# Simon_game.net
KiCad netlist of a schematic drawn in Altium Designer
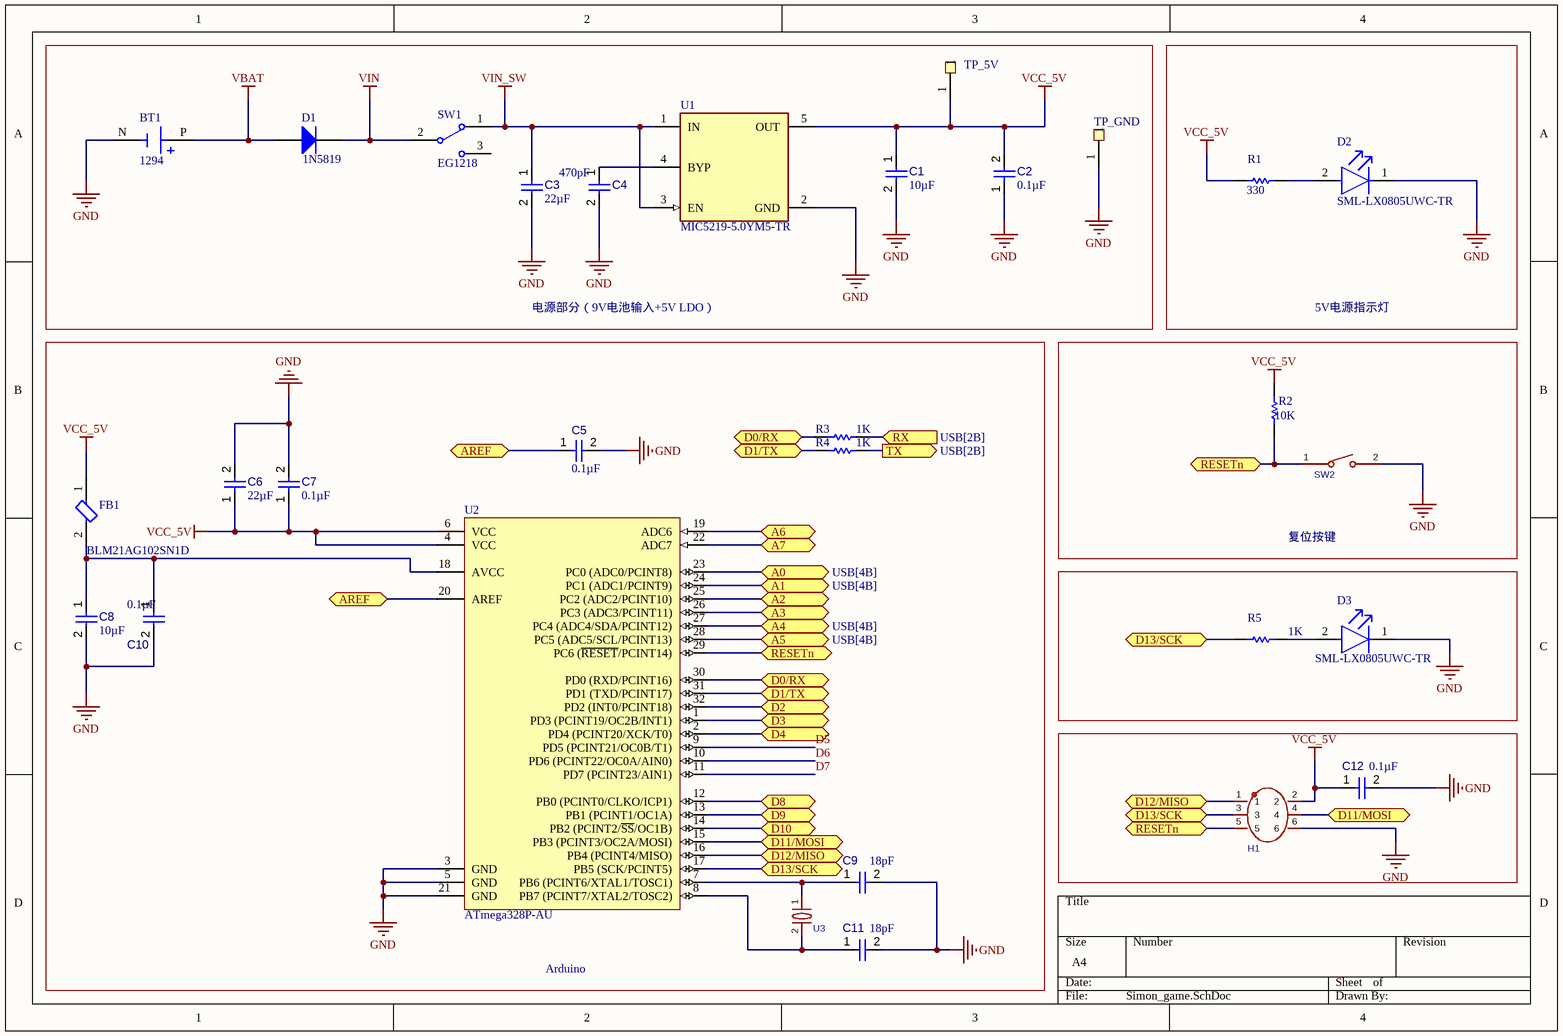
[diagram p0: Simon_game.SchDoc]

(export (version "E")
  (design (tool "Eeschema 10.0.6"))
  (components
    (comp (ref "BT1")
      (value "1294")
      (footprint "BAT_1294")
      (description "9 Volt Battery Holder- PC Terminals")
      (fields (field (name "MF") "Keystone Electronics"))
      (libsource (lib "keystone1294电池底座") (part "1294"))
    )
    (comp (ref "C1")
      (value "10µF")
      (footprint "CAPC2013X135X45NL10T25")
      (description "Chip Capacitor, 10 uF, +/- 10%, 16 V, 0805 (2012 Metric)")
      (fields (field (name "TOLERANCE") "10%") (field (name "Comment") "Capacitor 10 uF +/- 10% 16 V 0805"))
      (libsource (lib "新宇 付") (part "CAP-NP-2"))
    )
    (comp (ref "C2")
      (value "0.1µF")
      (footprint "CAPC2013X135X45NL10T25")
      (description "Chip Capacitor, 10 uF, +/- 10%, 16 V, 0805 (2012 Metric)")
      (fields (field (name "TOLERANCE") "10%") (field (name "Comment") "Capacitor 10 uF +/- 10% 16 V 0805"))
      (libsource (lib "新宇 付") (part "CAP-NP-2"))
    )
    (comp (ref "C3")
      (value "22µF")
      (footprint "CAPC2013X135X45NL10T25")
      (description "Chip Capacitor, 10 uF, +/- 10%, 16 V, 0805 (2012 Metric)")
      (fields (field (name "TOLERANCE") "10%") (field (name "Comment") "Capacitor 10 uF +/- 10% 16 V 0805"))
      (libsource (lib "新宇 付") (part "CAP-NP-2"))
    )
    (comp (ref "C4")
      (value "470pF")
      (footprint "CAPC2013X135X45NL10T25")
      (description "Chip Capacitor, 10 uF, +/- 10%, 16 V, 0805 (2012 Metric)")
      (fields (field (name "TOLERANCE") "10%") (field (name "Comment") "Capacitor 10 uF +/- 10% 16 V 0805"))
      (libsource (lib "新宇 付") (part "CAP-NP-2"))
    )
    (comp (ref "C5")
      (value "0.1µF")
      (footprint "CAPC2013X135X45NL10T25")
      (description "Chip Capacitor, 10 uF, +/- 10%, 16 V, 0805 (2012 Metric)")
      (fields (field (name "TOLERANCE") "10%") (field (name "Comment") "Capacitor 10 uF +/- 10% 16 V 0805"))
      (libsource (lib "新宇 付") (part "CAP-NP-2"))
    )
    (comp (ref "C6")
      (value "22µF")
      (footprint "CAPC2013X135X45NL10T25")
      (description "Chip Capacitor, 10 uF, +/- 10%, 16 V, 0805 (2012 Metric)")
      (fields (field (name "TOLERANCE") "10%") (field (name "Comment") "Capacitor 10 uF +/- 10% 16 V 0805"))
      (libsource (lib "新宇 付") (part "CAP-NP-2"))
    )
    (comp (ref "C7")
      (value "0.1µF")
      (footprint "CAPC2013X135X45NL10T25")
      (description "Chip Capacitor, 10 uF, +/- 10%, 16 V, 0805 (2012 Metric)")
      (fields (field (name "TOLERANCE") "10%") (field (name "Comment") "Capacitor 10 uF +/- 10% 16 V 0805"))
      (libsource (lib "新宇 付") (part "CAP-NP-2"))
    )
    (comp (ref "C8")
      (value "10µF")
      (footprint "CAPC2013X135X45NL10T25")
      (description "Chip Capacitor, 10 uF, +/- 10%, 16 V, 0805 (2012 Metric)")
      (fields (field (name "TOLERANCE") "10%") (field (name "Comment") "Capacitor 10 uF +/- 10% 16 V 0805"))
      (libsource (lib "新宇 付") (part "CAP-NP-2"))
    )
    (comp (ref "C9")
      (value "18pF")
      (footprint "CAPC2013X135X45NL10T25")
      (description "Chip Capacitor, 10 uF, +/- 10%, 16 V, 0805 (2012 Metric)")
      (fields (field (name "TOLERANCE") "10%") (field (name "Comment") "Capacitor 10 uF +/- 10% 16 V 0805"))
      (libsource (lib "新宇 付") (part "CAP-NP-2"))
    )
    (comp (ref "C10")
      (value "0.1µF")
      (footprint "CAPC2013X135X45NL10T25")
      (description "Chip Capacitor, 10 uF, +/- 10%, 16 V, 0805 (2012 Metric)")
      (fields (field (name "TOLERANCE") "10%") (field (name "Comment") "Capacitor 10 uF +/- 10% 16 V 0805"))
      (libsource (lib "新宇 付") (part "CAP-NP-2"))
    )
    (comp (ref "C11")
      (value "18pF")
      (footprint "CAPC2013X135X45NL10T25")
      (description "Chip Capacitor, 10 uF, +/- 10%, 16 V, 0805 (2012 Metric)")
      (fields (field (name "TOLERANCE") "10%") (field (name "Comment") "Capacitor 10 uF +/- 10% 16 V 0805"))
      (libsource (lib "新宇 付") (part "CAP-NP-2"))
    )
    (comp (ref "C12")
      (value "0.1µF")
      (footprint "CAPC2013X135X45NL10T25")
      (description "Chip Capacitor, 10 uF, +/- 10%, 16 V, 0805 (2012 Metric)")
      (fields (field (name "TOLERANCE") "10%") (field (name "Comment") "Capacitor 10 uF +/- 10% 16 V 0805"))
      (libsource (lib "新宇 付") (part "CAP-NP-2"))
    )
    (comp (ref "D1")
      (value "1N5819")
      (footprint "ONSC-AXIAL_LEAD-2-59-10_P")
      (description "Low Drop Power Schottky Rectifier, 40 V, 1 A, 2-Pin DO-41, RoHS")
      (fields (field (name "MANUFACTURER") "ON Semiconductor"))
      (libsource (lib "新宇 付") (part "D-AK-2"))
    )
    (comp (ref "D2")
      (value "SML-LX0805UWC-TR")
      (footprint "FP-SML-LX0805UWC-TR-MFG")
      (description "SML-LX0805UWC-TR White LED, 0805 Diffused, Rectangle Lens SMD package")
      (libsource (lib "Altium Content Vault") (part "8706943c75ba83719d021d2fdc84c58"))
    )
    (comp (ref "D3")
      (value "SML-LX0805UWC-TR")
      (footprint "FP-SML-LX0805UWC-TR-MFG")
      (description "SML-LX0805UWC-TR White LED, 0805 Diffused, Rectangle Lens SMD package")
      (libsource (lib "Altium Content Vault") (part "8706943c75ba83719d021d2fdc84c58"))
    )
    (comp (ref "FB1")
      (value "BLM21AG102SN1D")
      (footprint "FP-BLM21-0_2-t0_85-e0_5-MFG")
      (description "Chip Ferrite Bead, 0805, 1000Ω @ 100MHz, 0.27Ω, 25%, 600mA")
      (fields (field (name "TOLERANCE") "25%"))
      (libsource (lib "Altium Content Vault") (part "5f30dd21d616792df468990f7003faa"))
    )
    (comp (ref "H1")
      (value "PM2.54-2*3")
      (footprint "HDR-TH_6P-P2.54-V-F-R2-C3-S2.54")
      (libsource (lib "排母 2x3 2.54mm") (part "PM2.54-2*3"))
    )
    (comp (ref "R1")
      (value "330")
      (footprint "RESC2013X50X35ML15T15")
      (description "Chip Resistor, 0 Ohm, +/- 1%, 125 mW, -55 to 155 degC, 0805 (2012 Metric)")
      (fields (field (name "TOLERANCE") "1%") (field (name "POWER") "125mW"))
      (libsource (lib "新宇 付") (part "RES-2"))
    )
    (comp (ref "R2")
      (value "10K")
      (footprint "RESC2013X50X35ML15T15")
      (description "Chip Resistor, 0 Ohm, +/- 1%, 125 mW, -55 to 155 degC, 0805 (2012 Metric)")
      (fields (field (name "TOLERANCE") "1%") (field (name "POWER") "125mW"))
      (libsource (lib "新宇 付") (part "RES-2"))
    )
    (comp (ref "R3")
      (value "1K")
      (footprint "RESC2013X50X35ML15T15")
      (description "Chip Resistor, 0 Ohm, +/- 1%, 125 mW, -55 to 155 degC, 0805 (2012 Metric)")
      (fields (field (name "TOLERANCE") "1%") (field (name "POWER") "125mW"))
      (libsource (lib "新宇 付") (part "RES-2"))
    )
    (comp (ref "R4")
      (value "1K")
      (footprint "RESC2013X50X35ML15T15")
      (description "Chip Resistor, 0 Ohm, +/- 1%, 125 mW, -55 to 155 degC, 0805 (2012 Metric)")
      (fields (field (name "TOLERANCE") "1%") (field (name "POWER") "125mW"))
      (libsource (lib "新宇 付") (part "RES-2"))
    )
    (comp (ref "R5")
      (value "1K")
      (footprint "RESC2013X50X35ML15T15")
      (description "Chip Resistor, 0 Ohm, +/- 1%, 125 mW, -55 to 155 degC, 0805 (2012 Metric)")
      (fields (field (name "TOLERANCE") "1%") (field (name "POWER") "125mW"))
      (libsource (lib "新宇 付") (part "RES-2"))
    )
    (comp (ref "SW1")
      (value "EG1218")
      (footprint "ESWI-EG1218_V")
      (description "Slide Switch, 500 V, -20 to 70 degC, 3-Pin THD, RoHS")
      (libsource (lib "EG1218单刀双掷滑动开关") (part "CMP-1696-00002-1"))
    )
    (comp (ref "SW2")
      (value "TS-1088-AR02016")
      (footprint "SW-SMD_L3.9-W3.0-P4.45")
      (libsource (lib "Click_switch") (part "TS-1088-AR02016"))
    )
    (comp (ref "TP_5V")
      (value "TP_5V")
      (footprint "PCBComponent_1")
      (libsource (lib "testpoint") (part "Component_1"))
    )
    (comp (ref "TP_GND")
      (value "Component_1")
      (footprint "PCBComponent_1")
      (libsource (lib "testpoint") (part "Component_1"))
    )
    (comp (ref "U1")
      (value "MIC5219-5.0YM5-TR")
      (footprint "FP-SOT23-5LD-PL-1-MFG")
      (description "IC REG LINEAR 5V 500MA SOT23-5")
      (fields
        (field (name "OCTOPART") "https://octopart.com/mic5219-5.0ym5-tr-microchip-66802269")
        (field (name "MANUFACTURER") "Microchip Technology")
      )
      (libsource (lib "Altium Content Vault") (part "ef5decc81e5e4ee52dbbc9c70b739cf"))
    )
    (comp (ref "U2")
      (value "ATmega328P-AU")
      (footprint "32A_M")
      (libsource (lib "Altium Content Vault") (part "MC-8B-ATM48-SQ32"))
    )
    (comp (ref "U3")
      (value "ABLS-12.000MHZ-B4H-T")
      (footprint "CRYSTAL-SMD_L11.4-W4.7-LS12.7")
      (libsource (lib "12MHz_crystal_oscillator") (part "ABLS-12.000MHZ-B4H-T"))
    )
  )
  (nets
    (net (code "1") (name "/A0") (class "Default")
      (node (ref "U2") (pin "23") (pinfunction "PC0_(ADC0/PCINT8)_23") (pintype "bidirectional"))
    )
    (net (code "2") (name "/A1") (class "Default")
      (node (ref "U2") (pin "24") (pinfunction "PC1_(ADC1/PCINT9)_24") (pintype "bidirectional"))
    )
    (net (code "3") (name "/A2") (class "Default")
      (node (ref "U2") (pin "25") (pinfunction "PC2_(ADC2/PCINT10)_25") (pintype "bidirectional"))
    )
    (net (code "4") (name "/A3") (class "Default")
      (node (ref "U2") (pin "26") (pinfunction "PC3_(ADC3/PCINT11)_26") (pintype "bidirectional"))
    )
    (net (code "5") (name "/A4") (class "Default")
      (node (ref "U2") (pin "27") (pinfunction "PC4_(ADC4/SDA/PCINT12)_27") (pintype "bidirectional"))
    )
    (net (code "6") (name "/A5") (class "Default")
      (node (ref "U2") (pin "28") (pinfunction "PC5_(ADC5/SCL/PCINT13)_28") (pintype "bidirectional"))
    )
    (net (code "7") (name "/A6") (class "Default")
      (node (ref "U2") (pin "19") (pinfunction "ADC6_19") (pintype "input"))
    )
    (net (code "8") (name "/A7") (class "Default")
      (node (ref "U2") (pin "22") (pinfunction "ADC7_22") (pintype "input"))
    )
    (net (code "9") (name "/AREF") (class "Default")
      (node (ref "C5") (pin "1") (pinfunction "1_1") (pintype "passive"))
      (node (ref "U2") (pin "20") (pinfunction "AREF_20") (pintype "passive"))
    )
    (net (code "10") (name "/D0{slash}RX") (class "Default")
      (node (ref "R3") (pin "1") (pinfunction "1_1") (pintype "passive"))
      (node (ref "U2") (pin "30") (pinfunction "PD0_(RXD/PCINT16)_30") (pintype "bidirectional"))
    )
    (net (code "11") (name "/D1{slash}TX") (class "Default")
      (node (ref "R4") (pin "1") (pinfunction "1_1") (pintype "passive"))
      (node (ref "U2") (pin "31") (pinfunction "PD1_(TXD/PCINT17)_31") (pintype "bidirectional"))
    )
    (net (code "12") (name "/D2") (class "Default")
      (node (ref "U2") (pin "32") (pinfunction "PD2_(INT0/PCINT18)_32") (pintype "bidirectional"))
    )
    (net (code "13") (name "/D3") (class "Default")
      (node (ref "U2") (pin "1") (pinfunction "PD3_(PCINT19/OC2B/INT1)_1") (pintype "bidirectional"))
    )
    (net (code "14") (name "/D4") (class "Default")
      (node (ref "U2") (pin "2") (pinfunction "PD4_(PCINT20/XCK/T0)_2") (pintype "bidirectional"))
    )
    (net (code "15") (name "/D5") (class "Default")
      (node (ref "U2") (pin "9") (pinfunction "PD5_(PCINT21/OC0B/T1)_9") (pintype "bidirectional"))
    )
    (net (code "16") (name "/D6") (class "Default")
      (node (ref "U2") (pin "10") (pinfunction "PD6_(PCINT22/OC0A/AIN0)_10") (pintype "bidirectional"))
    )
    (net (code "17") (name "/D7") (class "Default")
      (node (ref "U2") (pin "11") (pinfunction "PD7_(PCINT23/AIN1)_11") (pintype "bidirectional"))
    )
    (net (code "18") (name "/D8") (class "Default")
      (node (ref "U2") (pin "12") (pinfunction "PB0_(PCINT0/CLKO/ICP1)_12") (pintype "bidirectional"))
    )
    (net (code "19") (name "/D9") (class "Default")
      (node (ref "U2") (pin "13") (pinfunction "PB1_(PCINT1/OC1A)_13") (pintype "bidirectional"))
    )
    (net (code "20") (name "/D10") (class "Default")
      (node (ref "U2") (pin "14") (pinfunction "PB2_(PCINT2/~{SS}/OC1B)_14") (pintype "bidirectional"))
    )
    (net (code "21") (name "/D11{slash}MOSI") (class "Default")
      (node (ref "H1") (pin "4") (pinfunction "4_4") (pintype "passive"))
      (node (ref "U2") (pin "15") (pinfunction "PB3_(PCINT3/OC2A/MOSI)_15") (pintype "bidirectional"))
    )
    (net (code "22") (name "/D12{slash}MISO") (class "Default")
      (node (ref "H1") (pin "1") (pinfunction "1_1") (pintype "passive"))
      (node (ref "U2") (pin "16") (pinfunction "PB4_(PCINT4/MISO)_16") (pintype "bidirectional"))
    )
    (net (code "23") (name "/D13{slash}SCK") (class "Default")
      (node (ref "H1") (pin "3") (pinfunction "3_3") (pintype "passive"))
      (node (ref "R5") (pin "1") (pinfunction "1_1") (pintype "passive"))
      (node (ref "U2") (pin "17") (pinfunction "PB5_(SCK/PCINT5)_17") (pintype "bidirectional"))
    )
    (net (code "24") (name "/RESETn") (class "Default")
      (node (ref "H1") (pin "5") (pinfunction "5_5") (pintype "passive"))
      (node (ref "R2") (pin "1") (pinfunction "1_1") (pintype "passive"))
      (node (ref "SW2") (pin "1") (pinfunction "1_1") (pintype "passive"))
      (node (ref "U2") (pin "29") (pinfunction "PC6_(~{RESET}/PCINT14)_29") (pintype "bidirectional"))
    )
    (net (code "25") (name "/RX") (class "Default")
      (node (ref "R3") (pin "2") (pinfunction "2_2") (pintype "passive"))
    )
    (net (code "26") (name "/TX") (class "Default")
      (node (ref "R4") (pin "2") (pinfunction "2_2") (pintype "passive"))
    )
    (net (code "27") (name "GND") (class "Default")
      (node (ref "BT1") (pin "N") (pinfunction "NEG_N") (pintype "passive"))
      (node (ref "C1") (pin "2") (pinfunction "2_2") (pintype "passive"))
      (node (ref "C10") (pin "2") (pinfunction "2_2") (pintype "passive"))
      (node (ref "C11") (pin "2") (pinfunction "2_2") (pintype "passive"))
      (node (ref "C12") (pin "2") (pinfunction "2_2") (pintype "passive"))
      (node (ref "C2") (pin "1") (pinfunction "1_1") (pintype "passive"))
      (node (ref "C3") (pin "2") (pinfunction "2_2") (pintype "passive"))
      (node (ref "C4") (pin "2") (pinfunction "2_2") (pintype "passive"))
      (node (ref "C5") (pin "2") (pinfunction "2_2") (pintype "passive"))
      (node (ref "C6") (pin "2") (pinfunction "2_2") (pintype "passive"))
      (node (ref "C7") (pin "2") (pinfunction "2_2") (pintype "passive"))
      (node (ref "C8") (pin "2") (pinfunction "2_2") (pintype "passive"))
      (node (ref "C9") (pin "2") (pinfunction "2_2") (pintype "passive"))
      (node (ref "D2") (pin "1") (pinfunction "C_1") (pintype "passive"))
      (node (ref "D3") (pin "1") (pinfunction "C_1") (pintype "passive"))
      (node (ref "H1") (pin "6") (pinfunction "6_6") (pintype "passive"))
      (node (ref "SW2") (pin "2") (pinfunction "2_2") (pintype "passive"))
      (node (ref "TP_GND") (pin "1") (pinfunction "1_1") (pintype "passive"))
      (node (ref "U1") (pin "2") (pinfunction "GND_2") (pintype "power_in"))
      (node (ref "U2") (pin "21") (pinfunction "GND_21") (pintype "power_in"))
      (node (ref "U2") (pin "3") (pinfunction "GND_3") (pintype "power_in"))
      (node (ref "U2") (pin "5") (pinfunction "GND_5") (pintype "power_in"))
    )
    (net (code "28") (name "Net-(D2-A)") (class "Default")
      (node (ref "D2") (pin "2") (pinfunction "A_2") (pintype "passive"))
      (node (ref "R1") (pin "2") (pinfunction "2_2") (pintype "passive"))
    )
    (net (code "29") (name "Net-(D3-A)") (class "Default")
      (node (ref "D3") (pin "2") (pinfunction "A_2") (pintype "passive"))
      (node (ref "R5") (pin "2") (pinfunction "2_2") (pintype "passive"))
    )
    (net (code "30") (name "Net-(U1-BYP)") (class "Default")
      (node (ref "C4") (pin "1") (pinfunction "1_1") (pintype "passive"))
      (node (ref "U1") (pin "4") (pinfunction "BYP_4") (pintype "passive"))
    )
    (net (code "31") (name "Net-(U2-AVCC)") (class "Default")
      (node (ref "C10") (pin "1") (pinfunction "1_1") (pintype "passive"))
      (node (ref "C8") (pin "1") (pinfunction "1_1") (pintype "passive"))
      (node (ref "FB1") (pin "2") (pinfunction "2_2") (pintype "passive"))
      (node (ref "U2") (pin "18") (pinfunction "AVCC_18") (pintype "power_in"))
    )
    (net (code "32") (name "Net-(U2-PB6_(PCINT6{slash}XTAL1{slash}TOSC1))") (class "Default")
      (node (ref "C9") (pin "1") (pinfunction "1_1") (pintype "passive"))
      (node (ref "U2") (pin "7") (pinfunction "PB6_(PCINT6/XTAL1/TOSC1)_7") (pintype "bidirectional"))
      (node (ref "U3") (pin "1") (pinfunction "1_1") (pintype "passive"))
    )
    (net (code "33") (name "Net-(U2-PB7_(PCINT7{slash}XTAL2{slash}TOSC2))") (class "Default")
      (node (ref "C11") (pin "1") (pinfunction "1_1") (pintype "passive"))
      (node (ref "U2") (pin "8") (pinfunction "PB7_(PCINT7/XTAL2/TOSC2)_8") (pintype "bidirectional"))
      (node (ref "U3") (pin "2") (pinfunction "GND_2") (pintype "passive"))
    )
    (net (code "34") (name "VBAT") (class "Default")
      (node (ref "BT1") (pin "P") (pinfunction "POS_P") (pintype "passive"))
      (node (ref "D1") (pin "1") (pinfunction "A_1") (pintype "passive"))
    )
    (net (code "35") (name "VCC_5V") (class "Default")
      (node (ref "C1") (pin "1") (pinfunction "1_1") (pintype "passive"))
      (node (ref "C12") (pin "1") (pinfunction "1_1") (pintype "passive"))
      (node (ref "C2") (pin "2") (pinfunction "2_2") (pintype "passive"))
      (node (ref "C6") (pin "1") (pinfunction "1_1") (pintype "passive"))
      (node (ref "C7") (pin "1") (pinfunction "1_1") (pintype "passive"))
      (node (ref "FB1") (pin "1") (pinfunction "1_1") (pintype "passive"))
      (node (ref "H1") (pin "2") (pinfunction "2_2") (pintype "passive"))
      (node (ref "R1") (pin "1") (pinfunction "1_1") (pintype "passive"))
      (node (ref "R2") (pin "2") (pinfunction "2_2") (pintype "passive"))
      (node (ref "TP_5V") (pin "1") (pinfunction "1_1") (pintype "passive"))
      (node (ref "U1") (pin "5") (pinfunction "OUT_5") (pintype "power_in"))
      (node (ref "U2") (pin "4") (pinfunction "VCC_4") (pintype "power_in"))
      (node (ref "U2") (pin "6") (pinfunction "VCC_6") (pintype "power_in"))
    )
    (net (code "36") (name "VIN") (class "Default")
      (node (ref "D1") (pin "2") (pinfunction "K_2") (pintype "passive"))
      (node (ref "SW1") (pin "2") (pinfunction "COM_2") (pintype "passive"))
    )
    (net (code "37") (name "VIN_SW") (class "Default")
      (node (ref "C3") (pin "1") (pinfunction "1_1") (pintype "passive"))
      (node (ref "SW1") (pin "1") (pinfunction "1_1") (pintype "passive"))
      (node (ref "U1") (pin "1") (pinfunction "IN_1") (pintype "power_in"))
      (node (ref "U1") (pin "3") (pinfunction "EN_3") (pintype "input"))
    )
    (net (code "38") (name "unconnected-(SW1-Pad3)") (class "Default")
      (node (ref "SW1") (pin "3") (pinfunction "3_3") (pintype "passive"))
    )
  )
)
